# input.net
KiCad netlist of a schematic drawn in Altium Designer
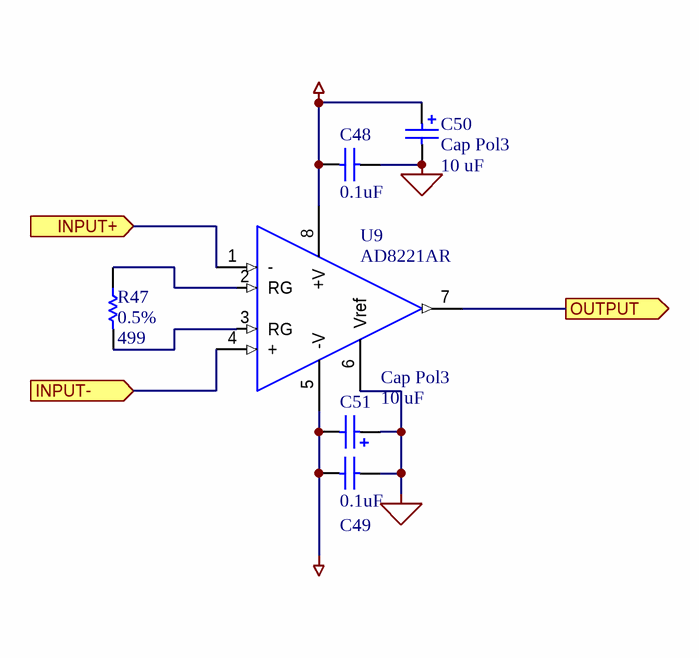
[diagram p0: input.SCHDOC]

(export (version "E")
  (design (tool "Eeschema 10.0.6"))
  (components
    (comp (ref "C48")
      (value "Cap")
      (footprint "CC1608-0603")
      (description "Capacitor")
      (fields
        (field (name "MANUFACTURER") "Generic Components")
        (field (name "ALTIUM_VALUE") "0.1uF")
        (field (name "PUBLISHER") "Altium Limited")
      )
      (libsource (lib "Miscellaneous Devices") (part "Cap"))
    )
    (comp (ref "C49")
      (value "Cap")
      (footprint "CC1608-0603")
      (description "Capacitor")
      (fields
        (field (name "MANUFACTURER") "Generic Components")
        (field (name "ALTIUM_VALUE") "0.1uF")
        (field (name "PUBLISHER") "Altium Limited")
      )
      (libsource (lib "Miscellaneous Devices") (part "Cap"))
    )
    (comp (ref "C50")
      (value "Cap Pol3")
      (footprint "TC3216-1206")
      (description "Polarized Capacitor (Surface Mount)")
      (fields
        (field (name "MANUFACTURER") "Generic Components")
        (field (name "ALTIUM_VALUE") "10 uF")
        (field (name "PUBLISHER") "Altium Limited")
      )
      (libsource (lib "Miscellaneous Devices") (part "Cap Pol3"))
    )
    (comp (ref "C51")
      (value "Cap Pol3")
      (footprint "TC3216-1206")
      (description "Polarized Capacitor (Surface Mount)")
      (fields
        (field (name "MANUFACTURER") "Generic Components")
        (field (name "ALTIUM_VALUE") "10 uF")
        (field (name "PUBLISHER") "Altium Limited")
      )
      (libsource (lib "Miscellaneous Devices") (part "Cap Pol3"))
    )
    (comp (ref "R47")
      (value "0.5%")
      (footprint "R2012-0805")
      (description "RR1220P-4990-D-M")
      (fields
        (field (name "MANUFACTURER") "Generic Components")
        (field (name "ALTIUM_VALUE") "499")
        (field (name "PUBLISHER") "Altium Limited")
      )
      (libsource (lib "Miscellaneous Devices") (part "Res1"))
    )
    (comp (ref "U9")
      (value "AD8221AR")
      (footprint "SO-G8")
      (description "AD8221 Precision Instrumentation Amplifier")
      (libsource (lib "My devices") (part "AD8221"))
    )
  )
  (nets
    (net (code "1") (name "/INPUT+") (class "Default")
      (node (ref "U9") (pin "1") (pinfunction "-_1") (pintype "input"))
    )
    (net (code "2") (name "/INPUT-") (class "Default")
      (node (ref "U9") (pin "4") (pinfunction "+_4") (pintype "input"))
    )
    (net (code "3") (name "/OUTPUT") (class "Default")
      (node (ref "U9") (pin "7") (pinfunction "Vout_7") (pintype "output"))
    )
    (net (code "4") (name "AVDD") (class "Default")
      (node (ref "C48") (pin "1") (pinfunction "1_1") (pintype "passive"))
      (node (ref "C50") (pin "1") (pinfunction "1_1") (pintype "passive"))
      (node (ref "U9") (pin "8") (pinfunction "+V_8") (pintype "power_in"))
    )
    (net (code "5") (name "AVSS") (class "Default")
      (node (ref "C49") (pin "1") (pinfunction "1_1") (pintype "passive"))
      (node (ref "C51") (pin "2") (pinfunction "2_2") (pintype "passive"))
      (node (ref "U9") (pin "5") (pinfunction "-V_5") (pintype "power_in"))
    )
    (net (code "6") (name "GND") (class "Default")
      (node (ref "C48") (pin "2") (pinfunction "2_2") (pintype "passive"))
      (node (ref "C49") (pin "2") (pinfunction "2_2") (pintype "passive"))
      (node (ref "C50") (pin "2") (pinfunction "2_2") (pintype "passive"))
      (node (ref "C51") (pin "1") (pinfunction "1_1") (pintype "passive"))
      (node (ref "U9") (pin "6") (pinfunction "Vref_6") (pintype "passive"))
    )
    (net (code "7") (name "Net-(R47-Pad1)") (class "Default")
      (node (ref "R47") (pin "1") (pinfunction "1_1") (pintype "passive"))
      (node (ref "U9") (pin "2") (pinfunction "RG_2") (pintype "input"))
    )
    (net (code "8") (name "Net-(R47-Pad2)") (class "Default")
      (node (ref "R47") (pin "2") (pinfunction "2_2") (pintype "passive"))
      (node (ref "U9") (pin "3") (pinfunction "RG_3") (pintype "input"))
    )
  )
)
